# Core_Power.net
KiCad netlist of a schematic drawn in Altium Designer
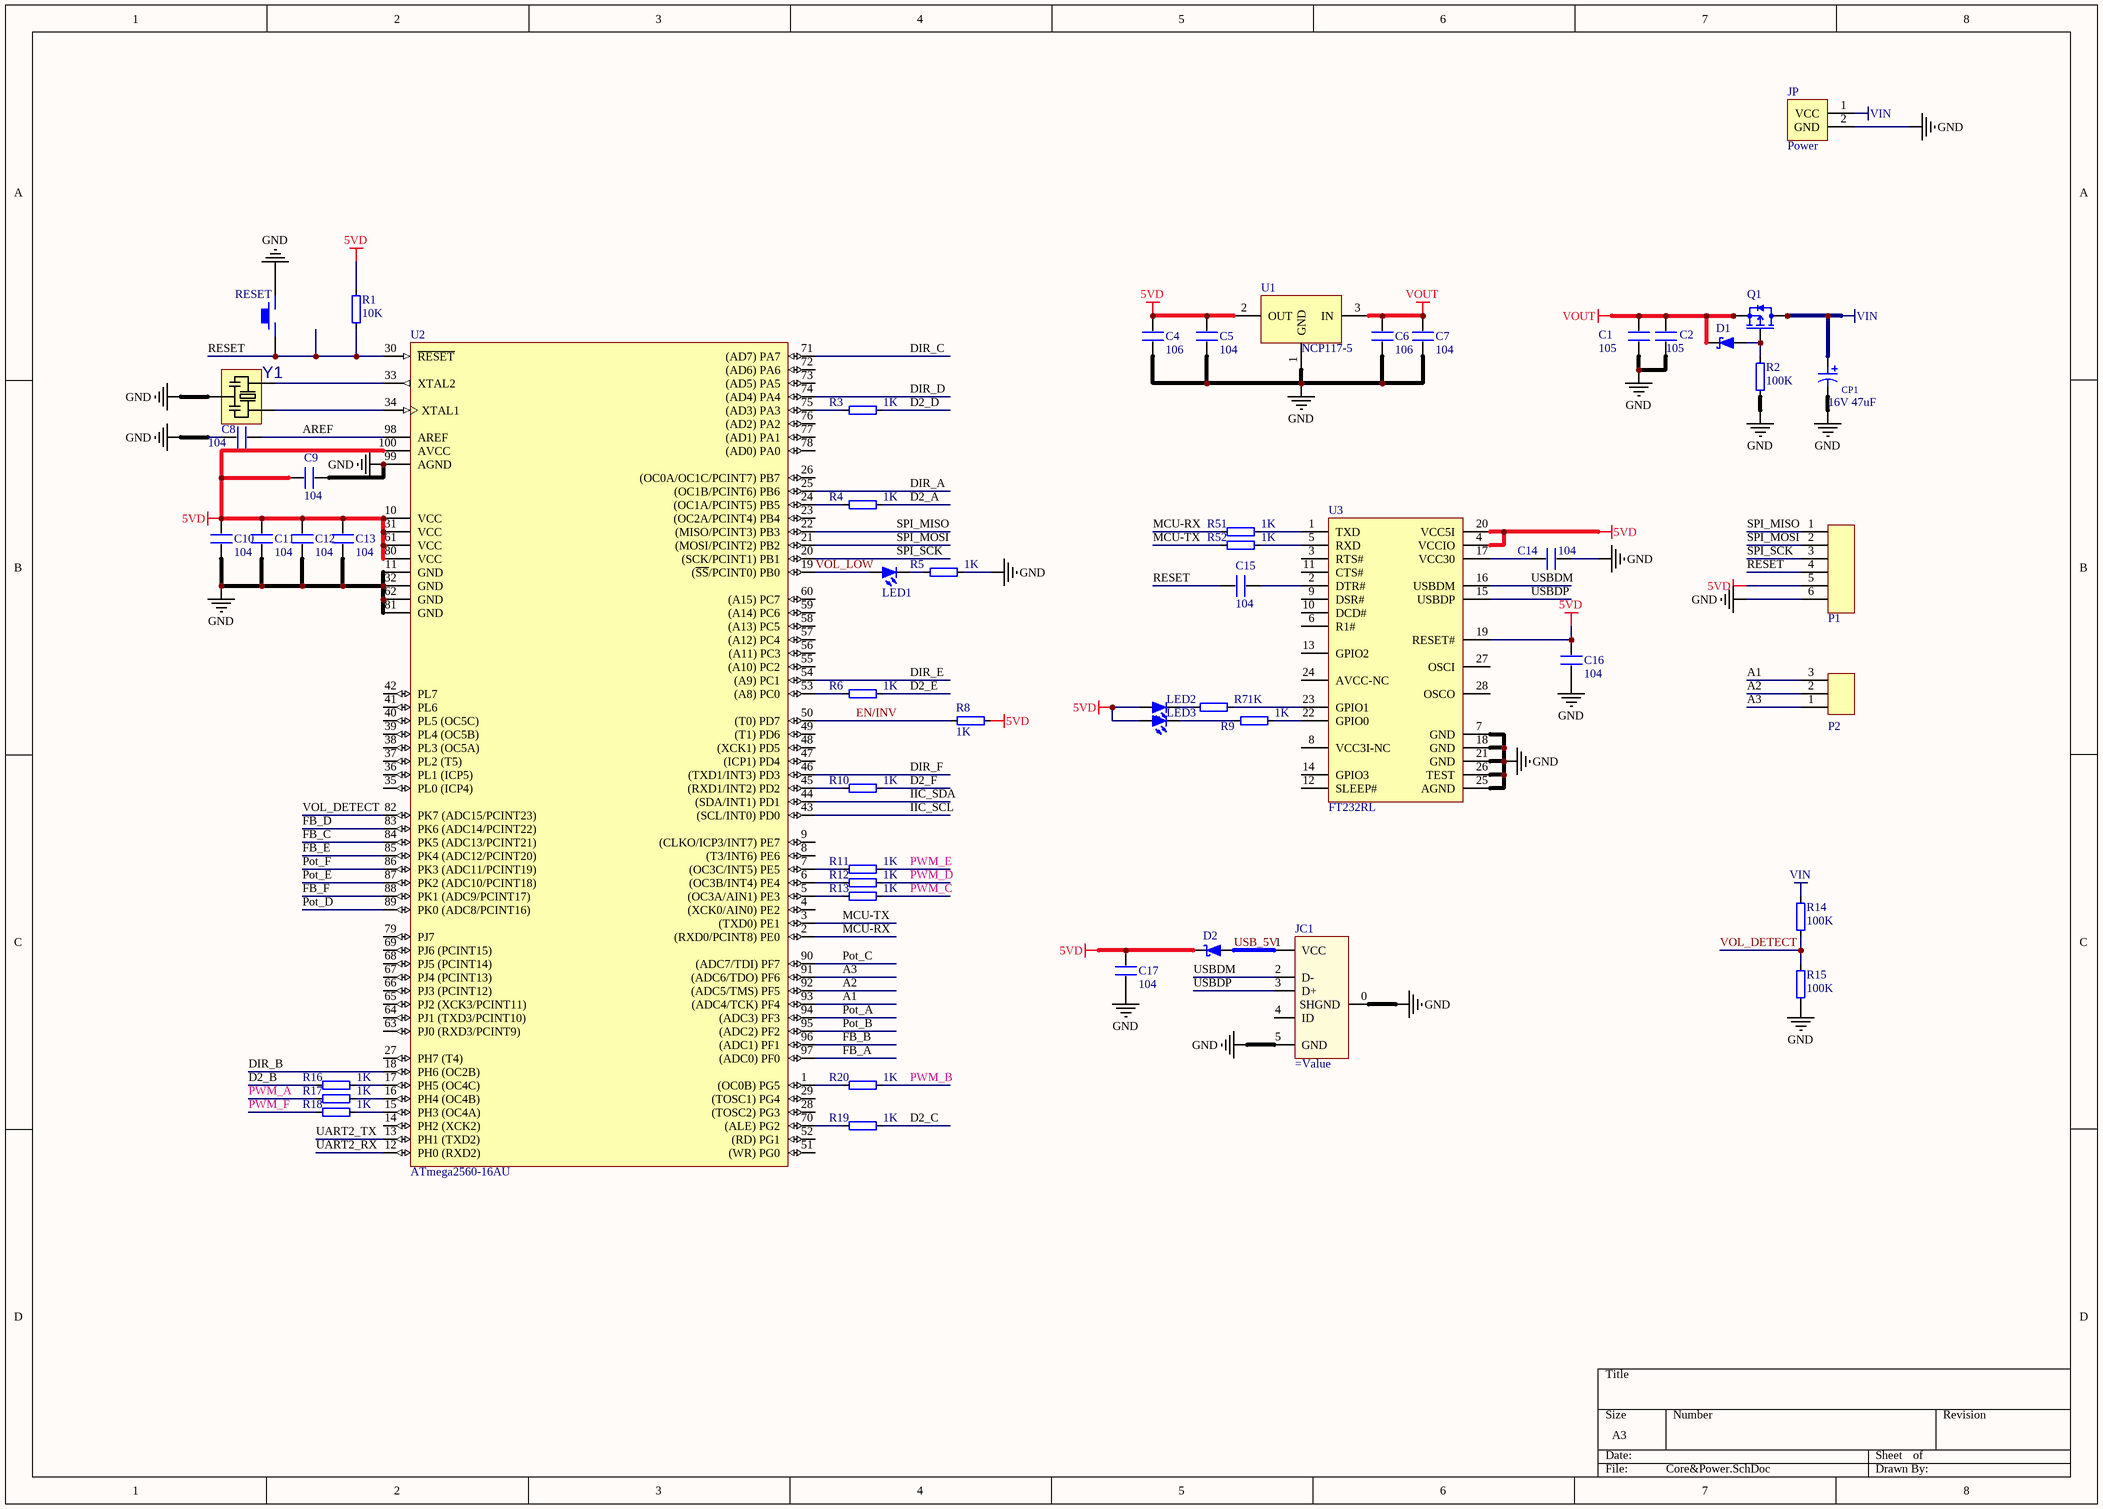
[diagram p0: Core&Power.SchDoc]

(export (version "E")
  (design (tool "Eeschema 10.0.6"))
  (components
    (comp (ref "C1") (value "105") (footprint "SM0603C") (libsource (lib "BAO") (part "C")))
    (comp (ref "C2") (value "105") (footprint "SM0603C") (libsource (lib "BAO") (part "C")))
    (comp (ref "C4") (value "106") (footprint "SM0603C") (libsource (lib "BAO") (part "C")))
    (comp (ref "C5") (value "104") (footprint "SM0603C") (libsource (lib "BAO") (part "C")))
    (comp (ref "C6") (value "106") (footprint "SM0603C") (libsource (lib "BAO") (part "C")))
    (comp (ref "C7") (value "104") (footprint "SM0603C") (libsource (lib "BAO") (part "C")))
    (comp (ref "C8") (value "104") (footprint "SM0603C") (libsource (lib "BAO") (part "C")))
    (comp (ref "C9") (value "104") (footprint "SM0603C") (libsource (lib "BAO") (part "C")))
    (comp (ref "C10") (value "104") (footprint "SM0603C") (libsource (lib "BAO") (part "C")))
    (comp (ref "C11") (value "104") (footprint "SM0603C") (libsource (lib "BAO") (part "C")))
    (comp (ref "C12") (value "104") (footprint "SM0603C") (libsource (lib "BAO") (part "C")))
    (comp (ref "C13") (value "104") (footprint "SM0603C") (libsource (lib "BAO") (part "C")))
    (comp (ref "C14") (value "104") (footprint "SM0603C") (libsource (lib "BAO") (part "C")))
    (comp (ref "C15") (value "104") (footprint "SM0603C") (libsource (lib "BAO") (part "C")))
    (comp (ref "C16") (value "104") (footprint "SM0603C") (libsource (lib "BAO") (part "C")))
    (comp (ref "C17") (value "104") (footprint "SM0603C") (libsource (lib "BAO") (part "C")))
    (comp (ref "CP1")
      (value "16V 47uF")
      (footprint "SMD5-Al")
      (description "Cap, 22uF, 20%, 16V")
      (libsource (lib "DigiMagusLib_CIS") (part "Cap Pol"))
    )
    (comp (ref "D1")
      (value "B5819W")
      (footprint "SOD-323")
      (description "Dio, Schottky, B5819W, 1A, 40V, SOD123, SSC")
      (fields (field (name "PART NUMBER") "2.1.4.21.0058190"))
      (libsource (lib "DigiMagusLib_CIS") (part "Diode Schottky"))
    )
    (comp (ref "D2")
      (value "B5819W")
      (footprint "SOD-323")
      (description "Dio, Schottky, B5819W, 1A, 40V, SOD123, SSC")
      (fields (field (name "PART NUMBER") "2.1.4.21.0058190"))
      (libsource (lib "DigiMagusLib_CIS") (part "Diode Schottky"))
    )
    (comp (ref "JC1")
      (value "~")
      (footprint "MICRO-USB2")
      (description "Mini USB Jack, SD-67803-002, Molex")
      (fields (field (name "PART NUMBER") "2.1.7.20.6780302"))
      (libsource (lib "DigiMagusLib_CIS") (part "USB_MINI_AB"))
    )
    (comp (ref "JP") (value "Power") (footprint "AM1015-M") (libsource (lib "Project") (part "Power")))
    (comp (ref "LED1")
      (value "Blue LED")
      (footprint "SM0805LED")
      (description "LED, Blue, 5mA, 0603")
      (fields (field (name "PART NUMBER") "2.1.4.10.0060330"))
      (libsource (lib "DigiMagusLib_CIS") (part "LED"))
    )
    (comp (ref "LED2")
      (value "Blue LED")
      (footprint "SM0805LED")
      (description "LED, Blue, 5mA, 0603")
      (fields (field (name "PART NUMBER") "2.1.4.10.0060330"))
      (libsource (lib "DigiMagusLib_CIS") (part "LED"))
    )
    (comp (ref "LED3")
      (value "Blue LED")
      (footprint "SM0805LED")
      (description "LED, Blue, 5mA, 0603")
      (fields (field (name "PART NUMBER") "2.1.4.10.0060330"))
      (libsource (lib "DigiMagusLib_CIS") (part "LED"))
    )
    (comp (ref "P1") (value "JC6") (footprint "HDR1X6") (libsource (lib "Project") (part "JC6")))
    (comp (ref "P2") (value "JC3") (footprint "HDR1X3") (libsource (lib "Schlib1") (part "JC3")))
    (comp (ref "Q1") (value "~") (description "Mos/P") (libsource (lib "Project") (part "IRF7842")))
    (comp (ref "R1") (value "10K") (footprint "SM0603R") (libsource (lib "电阻") (part "RES")))
    (comp (ref "R2") (value "100K") (footprint "SM0603R") (libsource (lib "电阻") (part "RES")))
    (comp (ref "R3") (value "1K") (footprint "SM0603R") (libsource (lib "电阻") (part "RES")))
    (comp (ref "R4") (value "1K") (footprint "SM0603R") (libsource (lib "电阻") (part "RES")))
    (comp (ref "R5") (value "1K") (footprint "SM0603R") (libsource (lib "电阻") (part "RES")))
    (comp (ref "R6") (value "1K") (footprint "SM0603R") (libsource (lib "电阻") (part "RES")))
    (comp (ref "R7") (value "1K") (footprint "SM0603R") (libsource (lib "电阻") (part "RES")))
    (comp (ref "R8") (value "1K") (footprint "SM0603R") (libsource (lib "电阻") (part "RES")))
    (comp (ref "R9") (value "1K") (footprint "SM0603R") (libsource (lib "电阻") (part "RES")))
    (comp (ref "R10") (value "1K") (footprint "SM0603R") (libsource (lib "电阻") (part "RES")))
    (comp (ref "R11") (value "1K") (footprint "SM0603R") (libsource (lib "电阻") (part "RES")))
    (comp (ref "R12") (value "1K") (footprint "SM0603R") (libsource (lib "电阻") (part "RES")))
    (comp (ref "R13") (value "1K") (footprint "SM0603R") (libsource (lib "电阻") (part "RES")))
    (comp (ref "R14") (value "100K") (footprint "SM0603R") (libsource (lib "电阻") (part "RES")))
    (comp (ref "R15") (value "100K") (footprint "SM0603R") (libsource (lib "电阻") (part "RES")))
    (comp (ref "R16") (value "1K") (footprint "SM0603R") (libsource (lib "电阻") (part "RES")))
    (comp (ref "R17") (value "1K") (footprint "SM0603R") (libsource (lib "电阻") (part "RES")))
    (comp (ref "R18") (value "1K") (footprint "SM0603R") (libsource (lib "电阻") (part "RES")))
    (comp (ref "R19") (value "1K") (footprint "SM0603R") (libsource (lib "电阻") (part "RES")))
    (comp (ref "R20") (value "1K") (footprint "SM0603R") (libsource (lib "电阻") (part "RES")))
    (comp (ref "R51") (value "1K") (footprint "SM0603R") (libsource (lib "电阻") (part "RES")))
    (comp (ref "R52") (value "1K") (footprint "SM0603R") (libsource (lib "电阻") (part "RES")))
    (comp (ref "RESET") (value "KEY_M") (footprint "SPNO_SMD") (libsource (lib "BAO") (part "KEY_M")))
    (comp (ref "U1") (value "NCP117-5") (footprint "SOT223-4") (libsource (lib "Schlib1") (part "NCP117-5")))
    (comp (ref "U2")
      (value "ATmega2560-16AU")
      (footprint "100A_N")
      (fields (field (name "PUBLISHER") "Altium Limited"))
      (libsource (lib "Schlib1") (part "ATmega2560-16AU"))
    )
    (comp (ref "U3") (value "FT232RL") (footprint "SSOP-28") (libsource (lib "Schlib1") (part "FT232RL")))
    (comp (ref "Y1")
      (value "CSTCE16M0V53-R0")
      (footprint "OSC_CSTCE16M0V53-R0")
      (description "Ceramic Resonator 16MHz ??0.5% (Tol) ??0.3% (Stability) 15pF 40Ohm 3-Pin CSMD T/R")
      (fields (field (name "MF") "Murata"))
      (libsource (lib "Schlib1") (part "CSTCE16M0V53-R0"))
    )
  )
  (nets
    (net (code "1") (name "/A1") (class "Default")
      (node (ref "P2") (pin "3") (pinfunction "3_3") (pintype "passive"))
      (node (ref "U2") (pin "93") (pinfunction "(ADC4/TCK)_PF4_93") (pintype "bidirectional"))
    )
    (net (code "2") (name "/A2") (class "Default")
      (node (ref "P2") (pin "2") (pinfunction "2_2") (pintype "passive"))
      (node (ref "U2") (pin "92") (pinfunction "(ADC5/TMS)_PF5_92") (pintype "bidirectional"))
    )
    (net (code "3") (name "/A3") (class "Default")
      (node (ref "P2") (pin "1") (pinfunction "1_1") (pintype "passive"))
      (node (ref "U2") (pin "91") (pinfunction "(ADC6/TDO)_PF6_91") (pintype "bidirectional"))
    )
    (net (code "4") (name "/AREF") (class "Default")
      (node (ref "C8") (pin "2") (pintype "passive"))
      (node (ref "U2") (pin "98") (pinfunction "AREF_98") (pintype "power_in"))
    )
    (net (code "5") (name "/D2_A") (class "Default")
      (node (ref "R4") (pin "2") (pinfunction "2_2") (pintype "passive"))
    )
    (net (code "6") (name "/D2_B") (class "Default")
      (node (ref "R16") (pin "2") (pinfunction "2_2") (pintype "passive"))
    )
    (net (code "7") (name "/D2_C") (class "Default")
      (node (ref "R19") (pin "2") (pinfunction "2_2") (pintype "passive"))
    )
    (net (code "8") (name "/D2_D") (class "Default")
      (node (ref "R3") (pin "2") (pinfunction "2_2") (pintype "passive"))
    )
    (net (code "9") (name "/D2_E") (class "Default")
      (node (ref "R6") (pin "2") (pinfunction "2_2") (pintype "passive"))
    )
    (net (code "10") (name "/D2_F") (class "Default")
      (node (ref "R10") (pin "2") (pinfunction "2_2") (pintype "passive"))
    )
    (net (code "11") (name "/DIR_A") (class "Default")
      (node (ref "U2") (pin "25") (pinfunction "(OC1B/PCINT6)_PB6_25") (pintype "bidirectional"))
    )
    (net (code "12") (name "/DIR_B") (class "Default")
      (node (ref "U2") (pin "18") (pinfunction "PH6_(OC2B)_18") (pintype "bidirectional"))
    )
    (net (code "13") (name "/DIR_C") (class "Default")
      (node (ref "U2") (pin "71") (pinfunction "(AD7)_PA7_71") (pintype "bidirectional"))
    )
    (net (code "14") (name "/DIR_D") (class "Default")
      (node (ref "U2") (pin "74") (pinfunction "(AD4)_PA4_74") (pintype "bidirectional"))
    )
    (net (code "15") (name "/DIR_E") (class "Default")
      (node (ref "U2") (pin "54") (pinfunction "(A9)_PC1_54") (pintype "bidirectional"))
    )
    (net (code "16") (name "/DIR_F") (class "Default")
      (node (ref "U2") (pin "46") (pinfunction "(TXD1/INT3)_PD3_46") (pintype "bidirectional"))
    )
    (net (code "17") (name "/EN{slash}INV") (class "Default")
      (node (ref "R8") (pin "2") (pinfunction "2_2") (pintype "passive"))
      (node (ref "U2") (pin "50") (pinfunction "(T0)_PD7_50") (pintype "bidirectional"))
    )
    (net (code "18") (name "/FB_A") (class "Default")
      (node (ref "U2") (pin "97") (pinfunction "(ADC0)_PF0_97") (pintype "bidirectional"))
    )
    (net (code "19") (name "/FB_B") (class "Default")
      (node (ref "U2") (pin "96") (pinfunction "(ADC1)_PF1_96") (pintype "bidirectional"))
    )
    (net (code "20") (name "/FB_C") (class "Default")
      (node (ref "U2") (pin "84") (pinfunction "PK5_(ADC13/PCINT21)_84") (pintype "bidirectional"))
    )
    (net (code "21") (name "/FB_D") (class "Default")
      (node (ref "U2") (pin "83") (pinfunction "PK6_(ADC14/PCINT22)_83") (pintype "bidirectional"))
    )
    (net (code "22") (name "/FB_E") (class "Default")
      (node (ref "U2") (pin "85") (pinfunction "PK4_(ADC12/PCINT20)_85") (pintype "bidirectional"))
    )
    (net (code "23") (name "/FB_F") (class "Default")
      (node (ref "U2") (pin "88") (pinfunction "PK1_(ADC9/PCINT17)_88") (pintype "bidirectional"))
    )
    (net (code "24") (name "/IIC_SCL") (class "Default")
      (node (ref "U2") (pin "43") (pinfunction "(SCL/INT0)_PD0_43") (pintype "bidirectional"))
    )
    (net (code "25") (name "/IIC_SDA") (class "Default")
      (node (ref "U2") (pin "44") (pinfunction "(SDA/INT1)_PD1_44") (pintype "bidirectional"))
    )
    (net (code "26") (name "/MCU-RX") (class "Default")
      (node (ref "R51") (pin "1") (pinfunction "1_1") (pintype "passive"))
      (node (ref "U2") (pin "2") (pinfunction "(RXD0/PCINT8)_PE0_2") (pintype "bidirectional"))
    )
    (net (code "27") (name "/MCU-TX") (class "Default")
      (node (ref "R52") (pin "1") (pinfunction "1_1") (pintype "passive"))
      (node (ref "U2") (pin "3") (pinfunction "(TXD0)_PE1_3") (pintype "bidirectional"))
    )
    (net (code "28") (name "/PWM_A") (class "Default")
      (node (ref "R17") (pin "1") (pinfunction "1_1") (pintype "passive"))
    )
    (net (code "29") (name "/PWM_B") (class "Default")
      (node (ref "R20") (pin "2") (pinfunction "2_2") (pintype "passive"))
    )
    (net (code "30") (name "/PWM_C") (class "Default")
      (node (ref "R13") (pin "2") (pinfunction "2_2") (pintype "passive"))
    )
    (net (code "31") (name "/PWM_D") (class "Default")
      (node (ref "R12") (pin "2") (pinfunction "2_2") (pintype "passive"))
    )
    (net (code "32") (name "/PWM_E") (class "Default")
      (node (ref "R11") (pin "2") (pinfunction "2_2") (pintype "passive"))
    )
    (net (code "33") (name "/PWM_F") (class "Default")
      (node (ref "R18") (pin "1") (pinfunction "1_1") (pintype "passive"))
    )
    (net (code "34") (name "/Pot_A") (class "Default")
      (node (ref "U2") (pin "94") (pinfunction "(ADC3)_PF3_94") (pintype "bidirectional"))
    )
    (net (code "35") (name "/Pot_B") (class "Default")
      (node (ref "U2") (pin "95") (pinfunction "(ADC2)_PF2_95") (pintype "bidirectional"))
    )
    (net (code "36") (name "/Pot_C") (class "Default")
      (node (ref "U2") (pin "90") (pinfunction "(ADC7/TDI)_PF7_90") (pintype "bidirectional"))
    )
    (net (code "37") (name "/Pot_D") (class "Default")
      (node (ref "U2") (pin "89") (pinfunction "PK0_(ADC8/PCINT16)_89") (pintype "bidirectional"))
    )
    (net (code "38") (name "/Pot_E") (class "Default")
      (node (ref "U2") (pin "87") (pinfunction "PK2_(ADC10/PCINT18)_87") (pintype "bidirectional"))
    )
    (net (code "39") (name "/Pot_F") (class "Default")
      (node (ref "U2") (pin "86") (pinfunction "PK3_(ADC11/PCINT19)_86") (pintype "bidirectional"))
    )
    (net (code "40") (name "/RESET") (class "Default")
      (node (ref "C15") (pin "2") (pintype "passive"))
      (node (ref "P1") (pin "4") (pinfunction "4_4") (pintype "passive"))
      (node (ref "R1") (pin "1") (pinfunction "1_1") (pintype "passive"))
      (node (ref "RESET") (pin "2") (pinfunction "2_2") (pintype "passive"))
      (node (ref "U2") (pin "30") (pinfunction "~{RESET}_30") (pintype "input"))
    )
    (net (code "41") (name "/SPI_MISO") (class "Default")
      (node (ref "P1") (pin "1") (pinfunction "1_1") (pintype "passive"))
      (node (ref "U2") (pin "22") (pinfunction "(MISO/PCINT3)_PB3_22") (pintype "bidirectional"))
    )
    (net (code "42") (name "/SPI_MOSI") (class "Default")
      (node (ref "P1") (pin "2") (pinfunction "2_2") (pintype "passive"))
      (node (ref "U2") (pin "21") (pinfunction "(MOSI/PCINT2)_PB2_21") (pintype "bidirectional"))
    )
    (net (code "43") (name "/SPI_SCK") (class "Default")
      (node (ref "P1") (pin "3") (pinfunction "3_3") (pintype "passive"))
      (node (ref "U2") (pin "20") (pinfunction "(SCK/PCINT1)_PB1_20") (pintype "bidirectional"))
    )
    (net (code "44") (name "/UART2_RX") (class "Default")
      (node (ref "U2") (pin "12") (pinfunction "PH0_(RXD2)_12") (pintype "bidirectional"))
    )
    (net (code "45") (name "/UART2_TX") (class "Default")
      (node (ref "U2") (pin "13") (pinfunction "PH1_(TXD2)_13") (pintype "bidirectional"))
    )
    (net (code "46") (name "/USBDM") (class "Default")
      (node (ref "JC1") (pin "2") (pinfunction "D-_2") (pintype "passive"))
      (node (ref "U3") (pin "16") (pinfunction "USBDM_16") (pintype "passive"))
    )
    (net (code "47") (name "/USBDP") (class "Default")
      (node (ref "JC1") (pin "3") (pinfunction "D+_3") (pintype "passive"))
      (node (ref "U3") (pin "15") (pinfunction "USBDP_15") (pintype "passive"))
    )
    (net (code "48") (name "/USB_5V") (class "Default")
      (node (ref "D2") (pin "2") (pinfunction "A_2") (pintype "passive"))
      (node (ref "JC1") (pin "1") (pinfunction "VCC_1") (pintype "passive"))
    )
    (net (code "49") (name "/VOL_DETECT") (class "Default")
      (node (ref "R14") (pin "1") (pinfunction "1_1") (pintype "passive"))
      (node (ref "R15") (pin "2") (pinfunction "2_2") (pintype "passive"))
      (node (ref "U2") (pin "82") (pinfunction "PK7_(ADC15/PCINT23)_82") (pintype "bidirectional"))
    )
    (net (code "50") (name "/VOL_LOW") (class "Default")
      (node (ref "LED1") (pin "2") (pinfunction "A_2") (pintype "passive"))
      (node (ref "U2") (pin "19") (pinfunction "(~{SS}/PCINT0)_PB0_19") (pintype "bidirectional"))
    )
    (net (code "51") (name "5VD") (class "Default")
      (node (ref "C10") (pin "1") (pintype "passive"))
      (node (ref "C11") (pin "1") (pintype "passive"))
      (node (ref "C12") (pin "1") (pintype "passive"))
      (node (ref "C13") (pin "1") (pintype "passive"))
      (node (ref "C16") (pin "2") (pintype "passive"))
      (node (ref "C17") (pin "2") (pintype "passive"))
      (node (ref "C4") (pin "2") (pintype "passive"))
      (node (ref "C5") (pin "2") (pintype "passive"))
      (node (ref "C9") (pin "2") (pintype "passive"))
      (node (ref "D2") (pin "1") (pinfunction "C_1") (pintype "passive"))
      (node (ref "LED2") (pin "2") (pinfunction "A_2") (pintype "passive"))
      (node (ref "LED3") (pin "2") (pinfunction "A_2") (pintype "passive"))
      (node (ref "P1") (pin "5") (pinfunction "5_5") (pintype "passive"))
      (node (ref "R1") (pin "2") (pinfunction "2_2") (pintype "passive"))
      (node (ref "R8") (pin "1") (pinfunction "1_1") (pintype "passive"))
      (node (ref "U1") (pin "2") (pinfunction "OUT_2") (pintype "passive"))
      (node (ref "U2") (pin "10") (pinfunction "VCC_10") (pintype "power_in"))
      (node (ref "U2") (pin "100") (pinfunction "AVCC_100") (pintype "power_in"))
      (node (ref "U2") (pin "31") (pinfunction "VCC_31") (pintype "power_in"))
      (node (ref "U2") (pin "61") (pinfunction "VCC_61") (pintype "power_in"))
      (node (ref "U2") (pin "80") (pinfunction "VCC_80") (pintype "power_in"))
      (node (ref "U3") (pin "19") (pinfunction "RESET#_19") (pintype "passive"))
      (node (ref "U3") (pin "20") (pinfunction "VCC5I_20") (pintype "passive"))
      (node (ref "U3") (pin "4") (pinfunction "VCCIO_4") (pintype "passive"))
    )
    (net (code "52") (name "GND") (class "Default")
      (node (ref "C1") (pin "1") (pintype "passive"))
      (node (ref "C10") (pin "2") (pintype "passive"))
      (node (ref "C11") (pin "2") (pintype "passive"))
      (node (ref "C12") (pin "2") (pintype "passive"))
      (node (ref "C13") (pin "2") (pintype "passive"))
      (node (ref "C14") (pin "2") (pintype "passive"))
      (node (ref "C16") (pin "1") (pintype "passive"))
      (node (ref "C17") (pin "1") (pintype "passive"))
      (node (ref "C2") (pin "1") (pintype "passive"))
      (node (ref "C4") (pin "1") (pintype "passive"))
      (node (ref "C5") (pin "1") (pintype "passive"))
      (node (ref "C6") (pin "1") (pintype "passive"))
      (node (ref "C7") (pin "1") (pintype "passive"))
      (node (ref "C8") (pin "1") (pintype "passive"))
      (node (ref "C9") (pin "1") (pintype "passive"))
      (node (ref "CP1") (pin "2") (pintype "passive"))
      (node (ref "JC1") (pin "0") (pinfunction "SHGND_0") (pintype "passive"))
      (node (ref "JC1") (pin "5") (pinfunction "GND_5") (pintype "passive"))
      (node (ref "JP") (pin "2") (pinfunction "GND_2") (pintype "passive"))
      (node (ref "P1") (pin "6") (pinfunction "6_6") (pintype "passive"))
      (node (ref "R15") (pin "1") (pinfunction "1_1") (pintype "passive"))
      (node (ref "R2") (pin "1") (pinfunction "1_1") (pintype "passive"))
      (node (ref "R5") (pin "2") (pinfunction "2_2") (pintype "passive"))
      (node (ref "RESET") (pin "1") (pinfunction "1_1") (pintype "passive"))
      (node (ref "U1") (pin "1") (pinfunction "GND_1") (pintype "passive"))
      (node (ref "U2") (pin "11") (pinfunction "GND_11") (pintype "power_in"))
      (node (ref "U2") (pin "32") (pinfunction "GND_32") (pintype "power_in"))
      (node (ref "U2") (pin "62") (pinfunction "GND_62") (pintype "power_in"))
      (node (ref "U2") (pin "81") (pinfunction "GND_81") (pintype "power_in"))
      (node (ref "U2") (pin "99") (pinfunction "AGND_99") (pintype "power_in"))
      (node (ref "U3") (pin "18") (pinfunction "GND_18") (pintype "passive"))
      (node (ref "U3") (pin "21") (pinfunction "GND_21") (pintype "passive"))
      (node (ref "U3") (pin "25") (pinfunction "AGND_25") (pintype "passive"))
      (node (ref "U3") (pin "26") (pinfunction "TEST_26") (pintype "passive"))
      (node (ref "U3") (pin "7") (pinfunction "GND_7") (pintype "passive"))
      (node (ref "Y1") (pin "2") (pinfunction "2_2") (pintype "power_in"))
    )
    (net (code "53") (name "Net-(D1-A)") (class "Default")
      (node (ref "D1") (pin "2") (pinfunction "A_2") (pintype "passive"))
      (node (ref "Q1") (pin "4") (pinfunction "G_4") (pintype "passive"))
      (node (ref "R2") (pin "2") (pinfunction "2_2") (pintype "passive"))
    )
    (net (code "54") (name "Net-(LED1-C)") (class "Default")
      (node (ref "LED1") (pin "1") (pinfunction "C_1") (pintype "passive"))
      (node (ref "R5") (pin "1") (pinfunction "1_1") (pintype "passive"))
    )
    (net (code "55") (name "Net-(LED2-C)") (class "Default")
      (node (ref "LED2") (pin "1") (pinfunction "C_1") (pintype "passive"))
      (node (ref "R7") (pin "1") (pinfunction "1_1") (pintype "passive"))
    )
    (net (code "56") (name "Net-(LED3-C)") (class "Default")
      (node (ref "LED3") (pin "1") (pinfunction "C_1") (pintype "passive"))
      (node (ref "R9") (pin "1") (pinfunction "1_1") (pintype "passive"))
    )
    (net (code "57") (name "Net-(U2-(A8)_PC0)") (class "Default")
      (node (ref "R6") (pin "1") (pinfunction "1_1") (pintype "passive"))
      (node (ref "U2") (pin "53") (pinfunction "(A8)_PC0_53") (pintype "bidirectional"))
    )
    (net (code "58") (name "Net-(U2-(AD3)_PA3)") (class "Default")
      (node (ref "R3") (pin "1") (pinfunction "1_1") (pintype "passive"))
      (node (ref "U2") (pin "75") (pinfunction "(AD3)_PA3_75") (pintype "bidirectional"))
    )
    (net (code "59") (name "Net-(U2-(ALE)_PG2)") (class "Default")
      (node (ref "R19") (pin "1") (pinfunction "1_1") (pintype "passive"))
      (node (ref "U2") (pin "70") (pinfunction "(ALE)_PG2_70") (pintype "bidirectional"))
    )
    (net (code "60") (name "Net-(U2-(OC0B)_PG5)") (class "Default")
      (node (ref "R20") (pin "1") (pinfunction "1_1") (pintype "passive"))
      (node (ref "U2") (pin "1") (pinfunction "(OC0B)_PG5_1") (pintype "bidirectional"))
    )
    (net (code "61") (name "Net-(U2-(OC1A{slash}PCINT5)_PB5)") (class "Default")
      (node (ref "R4") (pin "1") (pinfunction "1_1") (pintype "passive"))
      (node (ref "U2") (pin "24") (pinfunction "(OC1A/PCINT5)_PB5_24") (pintype "bidirectional"))
    )
    (net (code "62") (name "Net-(U2-(OC3A{slash}AIN1)_PE3)") (class "Default")
      (node (ref "R13") (pin "1") (pinfunction "1_1") (pintype "passive"))
      (node (ref "U2") (pin "5") (pinfunction "(OC3A/AIN1)_PE3_5") (pintype "bidirectional"))
    )
    (net (code "63") (name "Net-(U2-(OC3B{slash}INT4)_PE4)") (class "Default")
      (node (ref "R12") (pin "1") (pinfunction "1_1") (pintype "passive"))
      (node (ref "U2") (pin "6") (pinfunction "(OC3B/INT4)_PE4_6") (pintype "bidirectional"))
    )
    (net (code "64") (name "Net-(U2-(OC3C{slash}INT5)_PE5)") (class "Default")
      (node (ref "R11") (pin "1") (pinfunction "1_1") (pintype "passive"))
      (node (ref "U2") (pin "7") (pinfunction "(OC3C/INT5)_PE5_7") (pintype "bidirectional"))
    )
    (net (code "65") (name "Net-(U2-(RXD1{slash}INT2)_PD2)") (class "Default")
      (node (ref "R10") (pin "1") (pinfunction "1_1") (pintype "passive"))
      (node (ref "U2") (pin "45") (pinfunction "(RXD1/INT2)_PD2_45") (pintype "bidirectional"))
    )
    (net (code "66") (name "Net-(U2-PH3_(OC4A))") (class "Default")
      (node (ref "R18") (pin "2") (pinfunction "2_2") (pintype "passive"))
      (node (ref "U2") (pin "15") (pinfunction "PH3_(OC4A)_15") (pintype "bidirectional"))
    )
    (net (code "67") (name "Net-(U2-PH4_(OC4B))") (class "Default")
      (node (ref "R17") (pin "2") (pinfunction "2_2") (pintype "passive"))
      (node (ref "U2") (pin "16") (pinfunction "PH4_(OC4B)_16") (pintype "bidirectional"))
    )
    (net (code "68") (name "Net-(U2-PH5_(OC4C))") (class "Default")
      (node (ref "R16") (pin "1") (pinfunction "1_1") (pintype "passive"))
      (node (ref "U2") (pin "17") (pinfunction "PH5_(OC4C)_17") (pintype "bidirectional"))
    )
    (net (code "69") (name "Net-(U2-XTAL1)") (class "Default")
      (node (ref "U2") (pin "34") (pinfunction "XTAL1_34") (pintype "input"))
      (node (ref "Y1") (pin "1") (pinfunction "1_1") (pintype "passive"))
    )
    (net (code "70") (name "Net-(U2-XTAL2)") (class "Default")
      (node (ref "U2") (pin "33") (pinfunction "XTAL2_33") (pintype "output"))
      (node (ref "Y1") (pin "3") (pinfunction "3_3") (pintype "passive"))
    )
    (net (code "71") (name "Net-(U3-DTR#)") (class "Default")
      (node (ref "C15") (pin "1") (pintype "passive"))
      (node (ref "U3") (pin "2") (pinfunction "DTR#_2") (pintype "passive"))
    )
    (net (code "72") (name "Net-(U3-GPIO0)") (class "Default")
      (node (ref "R9") (pin "2") (pinfunction "2_2") (pintype "passive"))
      (node (ref "U3") (pin "22") (pinfunction "GPIO0_22") (pintype "passive"))
    )
    (net (code "73") (name "Net-(U3-GPIO1)") (class "Default")
      (node (ref "R7") (pin "2") (pinfunction "2_2") (pintype "passive"))
      (node (ref "U3") (pin "23") (pinfunction "GPIO1_23") (pintype "passive"))
    )
    (net (code "74") (name "Net-(U3-RXD)") (class "Default")
      (node (ref "R52") (pin "2") (pinfunction "2_2") (pintype "passive"))
      (node (ref "U3") (pin "5") (pinfunction "RXD_5") (pintype "passive"))
    )
    (net (code "75") (name "Net-(U3-TXD)") (class "Default")
      (node (ref "R51") (pin "2") (pinfunction "2_2") (pintype "passive"))
      (node (ref "U3") (pin "1") (pinfunction "TXD_1") (pintype "passive"))
    )
    (net (code "76") (name "Net-(U3-VCC30)") (class "Default")
      (node (ref "C14") (pin "1") (pintype "passive"))
      (node (ref "U3") (pin "17") (pinfunction "VCC30_17") (pintype "passive"))
    )
    (net (code "77") (name "VIN") (class "Default")
      (node (ref "CP1") (pin "1") (pintype "passive"))
      (node (ref "JP") (pin "1") (pinfunction "VCC_1") (pintype "passive"))
      (node (ref "Q1") (pin "5") (pinfunction "D_5") (pintype "passive"))
      (node (ref "Q1") (pin "6") (pinfunction "D_6") (pintype "passive"))
      (node (ref "Q1") (pin "7") (pinfunction "D_7") (pintype "passive"))
      (node (ref "Q1") (pin "8") (pinfunction "D_8") (pintype "passive"))
      (node (ref "R14") (pin "2") (pinfunction "2_2") (pintype "passive"))
    )
    (net (code "78") (name "VOUT") (class "Default")
      (node (ref "C1") (pin "2") (pintype "passive"))
      (node (ref "C2") (pin "2") (pintype "passive"))
      (node (ref "C6") (pin "2") (pintype "passive"))
      (node (ref "C7") (pin "2") (pintype "passive"))
      (node (ref "D1") (pin "1") (pinfunction "C_1") (pintype "passive"))
      (node (ref "Q1") (pin "1") (pinfunction "S_1") (pintype "passive"))
      (node (ref "Q1") (pin "2") (pinfunction "S_2") (pintype "passive"))
      (node (ref "Q1") (pin "3") (pinfunction "S_3") (pintype "passive"))
      (node (ref "U1") (pin "3") (pinfunction "IN_3") (pintype "passive"))
    )
    (net (code "79") (name "unconnected-(JC1-ID-Pad4)") (class "Default")
      (node (ref "JC1") (pin "4") (pinfunction "ID_4") (pintype "passive"))
    )
    (net (code "80") (name "unconnected-(U2-(A10)_PC2-Pad55)") (class "Default")
      (node (ref "U2") (pin "55") (pinfunction "(A10)_PC2_55") (pintype "bidirectional"))
    )
    (net (code "81") (name "unconnected-(U2-(A11)_PC3-Pad56)") (class "Default")
      (node (ref "U2") (pin "56") (pinfunction "(A11)_PC3_56") (pintype "bidirectional"))
    )
    (net (code "82") (name "unconnected-(U2-(A12)_PC4-Pad57)") (class "Default")
      (node (ref "U2") (pin "57") (pinfunction "(A12)_PC4_57") (pintype "bidirectional"))
    )
    (net (code "83") (name "unconnected-(U2-(A13)_PC5-Pad58)") (class "Default")
      (node (ref "U2") (pin "58") (pinfunction "(A13)_PC5_58") (pintype "bidirectional"))
    )
    (net (code "84") (name "unconnected-(U2-(A14)_PC6-Pad59)") (class "Default")
      (node (ref "U2") (pin "59") (pinfunction "(A14)_PC6_59") (pintype "bidirectional"))
    )
    (net (code "85") (name "unconnected-(U2-(A15)_PC7-Pad60)") (class "Default")
      (node (ref "U2") (pin "60") (pinfunction "(A15)_PC7_60") (pintype "bidirectional"))
    )
    (net (code "86") (name "unconnected-(U2-(AD0)_PA0-Pad78)") (class "Default")
      (node (ref "U2") (pin "78") (pinfunction "(AD0)_PA0_78") (pintype "bidirectional"))
    )
    (net (code "87") (name "unconnected-(U2-(AD1)_PA1-Pad77)") (class "Default")
      (node (ref "U2") (pin "77") (pinfunction "(AD1)_PA1_77") (pintype "bidirectional"))
    )
    (net (code "88") (name "unconnected-(U2-(AD2)_PA2-Pad76)") (class "Default")
      (node (ref "U2") (pin "76") (pinfunction "(AD2)_PA2_76") (pintype "bidirectional"))
    )
    (net (code "89") (name "unconnected-(U2-(AD5)_PA5-Pad73)") (class "Default")
      (node (ref "U2") (pin "73") (pinfunction "(AD5)_PA5_73") (pintype "bidirectional"))
    )
    (net (code "90") (name "unconnected-(U2-(AD6)_PA6-Pad72)") (class "Default")
      (node (ref "U2") (pin "72") (pinfunction "(AD6)_PA6_72") (pintype "bidirectional"))
    )
    (net (code "91") (name "unconnected-(U2-(CLKO{slash}ICP3{slash}INT7)_PE7-Pad9)") (class "Default")
      (node (ref "U2") (pin "9") (pinfunction "(CLKO/ICP3/INT7)_PE7_9") (pintype "bidirectional"))
    )
    (net (code "92") (name "unconnected-(U2-(ICP1)_PD4-Pad47)") (class "Default")
      (node (ref "U2") (pin "47") (pinfunction "(ICP1)_PD4_47") (pintype "bidirectional"))
    )
    (net (code "93") (name "unconnected-(U2-(OC0A{slash}OC1C{slash}PCINT7)_PB7-Pad26)") (class "Default")
      (node (ref "U2") (pin "26") (pinfunction "(OC0A/OC1C/PCINT7)_PB7_26") (pintype "bidirectional"))
    )
    (net (code "94") (name "unconnected-(U2-(OC2A{slash}PCINT4)_PB4-Pad23)") (class "Default")
      (node (ref "U2") (pin "23") (pinfunction "(OC2A/PCINT4)_PB4_23") (pintype "bidirectional"))
    )
    (net (code "95") (name "unconnected-(U2-(RD)_PG1-Pad52)") (class "Default")
      (node (ref "U2") (pin "52") (pinfunction "(RD)_PG1_52") (pintype "bidirectional"))
    )
    (net (code "96") (name "unconnected-(U2-(T1)_PD6-Pad49)") (class "Default")
      (node (ref "U2") (pin "49") (pinfunction "(T1)_PD6_49") (pintype "bidirectional"))
    )
    (net (code "97") (name "unconnected-(U2-(T3{slash}INT6)_PE6-Pad8)") (class "Default")
      (node (ref "U2") (pin "8") (pinfunction "(T3/INT6)_PE6_8") (pintype "bidirectional"))
    )
    (net (code "98") (name "unconnected-(U2-(TOSC1)_PG4-Pad29)") (class "Default")
      (node (ref "U2") (pin "29") (pinfunction "(TOSC1)_PG4_29") (pintype "bidirectional"))
    )
    (net (code "99") (name "unconnected-(U2-(TOSC2)_PG3-Pad28)") (class "Default")
      (node (ref "U2") (pin "28") (pinfunction "(TOSC2)_PG3_28") (pintype "bidirectional"))
    )
    (net (code "100") (name "unconnected-(U2-(WR)_PG0-Pad51)") (class "Default")
      (node (ref "U2") (pin "51") (pinfunction "(WR)_PG0_51") (pintype "bidirectional"))
    )
    (net (code "101") (name "unconnected-(U2-(XCK0{slash}AIN0)_PE2-Pad4)") (class "Default")
      (node (ref "U2") (pin "4") (pinfunction "(XCK0/AIN0)_PE2_4") (pintype "bidirectional"))
    )
    (net (code "102") (name "unconnected-(U2-(XCK1)_PD5-Pad48)") (class "Default")
      (node (ref "U2") (pin "48") (pinfunction "(XCK1)_PD5_48") (pintype "bidirectional"))
    )
    (net (code "103") (name "unconnected-(U2-PH2_(XCK2)-Pad14)") (class "Default")
      (node (ref "U2") (pin "14") (pinfunction "PH2_(XCK2)_14") (pintype "bidirectional"))
    )
    (net (code "104") (name "unconnected-(U2-PH7_(T4)-Pad27)") (class "Default")
      (node (ref "U2") (pin "27") (pinfunction "PH7_(T4)_27") (pintype "bidirectional"))
    )
    (net (code "105") (name "unconnected-(U2-PJ0_(RXD3{slash}PCINT9)-Pad63)") (class "Default")
      (node (ref "U2") (pin "63") (pinfunction "PJ0_(RXD3/PCINT9)_63") (pintype "bidirectional"))
    )
    (net (code "106") (name "unconnected-(U2-PJ1_(TXD3{slash}PCINT10)-Pad64)") (class "Default")
      (node (ref "U2") (pin "64") (pinfunction "PJ1_(TXD3/PCINT10)_64") (pintype "bidirectional"))
    )
    (net (code "107") (name "unconnected-(U2-PJ2_(XCK3{slash}PCINT11)-Pad65)") (class "Default")
      (node (ref "U2") (pin "65") (pinfunction "PJ2_(XCK3/PCINT11)_65") (pintype "bidirectional"))
    )
    (net (code "108") (name "unconnected-(U2-PJ3_(PCINT12)-Pad66)") (class "Default")
      (node (ref "U2") (pin "66") (pinfunction "PJ3_(PCINT12)_66") (pintype "bidirectional"))
    )
    (net (code "109") (name "unconnected-(U2-PJ4_(PCINT13)-Pad67)") (class "Default")
      (node (ref "U2") (pin "67") (pinfunction "PJ4_(PCINT13)_67") (pintype "bidirectional"))
    )
    (net (code "110") (name "unconnected-(U2-PJ5_(PCINT14)-Pad68)") (class "Default")
      (node (ref "U2") (pin "68") (pinfunction "PJ5_(PCINT14)_68") (pintype "bidirectional"))
    )
    (net (code "111") (name "unconnected-(U2-PJ6_(PCINT15)-Pad69)") (class "Default")
      (node (ref "U2") (pin "69") (pinfunction "PJ6_(PCINT15)_69") (pintype "bidirectional"))
    )
    (net (code "112") (name "unconnected-(U2-PJ7-Pad79)") (class "Default")
      (node (ref "U2") (pin "79") (pinfunction "PJ7_79") (pintype "bidirectional"))
    )
    (net (code "113") (name "unconnected-(U2-PL0_(ICP4)-Pad35)") (class "Default")
      (node (ref "U2") (pin "35") (pinfunction "PL0_(ICP4)_35") (pintype "bidirectional"))
    )
    (net (code "114") (name "unconnected-(U2-PL1_(ICP5)-Pad36)") (class "Default")
      (node (ref "U2") (pin "36") (pinfunction "PL1_(ICP5)_36") (pintype "bidirectional"))
    )
    (net (code "115") (name "unconnected-(U2-PL2_(T5)-Pad37)") (class "Default")
      (node (ref "U2") (pin "37") (pinfunction "PL2_(T5)_37") (pintype "bidirectional"))
    )
    (net (code "116") (name "unconnected-(U2-PL3_(OC5A)-Pad38)") (class "Default")
      (node (ref "U2") (pin "38") (pinfunction "PL3_(OC5A)_38") (pintype "bidirectional"))
    )
    (net (code "117") (name "unconnected-(U2-PL4_(OC5B)-Pad39)") (class "Default")
      (node (ref "U2") (pin "39") (pinfunction "PL4_(OC5B)_39") (pintype "bidirectional"))
    )
    (net (code "118") (name "unconnected-(U2-PL5_(OC5C)-Pad40)") (class "Default")
      (node (ref "U2") (pin "40") (pinfunction "PL5_(OC5C)_40") (pintype "bidirectional"))
    )
    (net (code "119") (name "unconnected-(U2-PL6-Pad41)") (class "Default")
      (node (ref "U2") (pin "41") (pinfunction "PL6_41") (pintype "bidirectional"))
    )
    (net (code "120") (name "unconnected-(U2-PL7-Pad42)") (class "Default")
      (node (ref "U2") (pin "42") (pinfunction "PL7_42") (pintype "bidirectional"))
    )
    (net (code "121") (name "unconnected-(U3-AVCC-NC-Pad24)") (class "Default")
      (node (ref "U3") (pin "24") (pinfunction "AVCC-NC_24") (pintype "passive"))
    )
    (net (code "122") (name "unconnected-(U3-CTS#-Pad11)") (class "Default")
      (node (ref "U3") (pin "11") (pinfunction "CTS#_11") (pintype "passive"))
    )
    (net (code "123") (name "unconnected-(U3-DCD#-Pad10)") (class "Default")
      (node (ref "U3") (pin "10") (pinfunction "DCD#_10") (pintype "passive"))
    )
    (net (code "124") (name "unconnected-(U3-DSR#-Pad9)") (class "Default")
      (node (ref "U3") (pin "9") (pinfunction "DSR#_9") (pintype "passive"))
    )
    (net (code "125") (name "unconnected-(U3-GPIO2-Pad13)") (class "Default")
      (node (ref "U3") (pin "13") (pinfunction "GPIO2_13") (pintype "passive"))
    )
    (net (code "126") (name "unconnected-(U3-GPIO3-Pad14)") (class "Default")
      (node (ref "U3") (pin "14") (pinfunction "GPIO3_14") (pintype "passive"))
    )
    (net (code "127") (name "unconnected-(U3-OSCI-Pad27)") (class "Default")
      (node (ref "U3") (pin "27") (pinfunction "OSCI_27") (pintype "passive"))
    )
    (net (code "128") (name "unconnected-(U3-OSCO-Pad28)") (class "Default")
      (node (ref "U3") (pin "28") (pinfunction "OSCO_28") (pintype "passive"))
    )
    (net (code "129") (name "unconnected-(U3-R1#-Pad6)") (class "Default")
      (node (ref "U3") (pin "6") (pinfunction "R1#_6") (pintype "passive"))
    )
    (net (code "130") (name "unconnected-(U3-RTS#-Pad3)") (class "Default")
      (node (ref "U3") (pin "3") (pinfunction "RTS#_3") (pintype "passive"))
    )
    (net (code "131") (name "unconnected-(U3-SLEEP#-Pad12)") (class "Default")
      (node (ref "U3") (pin "12") (pinfunction "SLEEP#_12") (pintype "passive"))
    )
    (net (code "132") (name "unconnected-(U3-VCC3I-NC-Pad8)") (class "Default")
      (node (ref "U3") (pin "8") (pinfunction "VCC3I-NC_8") (pintype "passive"))
    )
  )
)
